# oled.net
KiCad netlist of a schematic drawn in Altium Designer
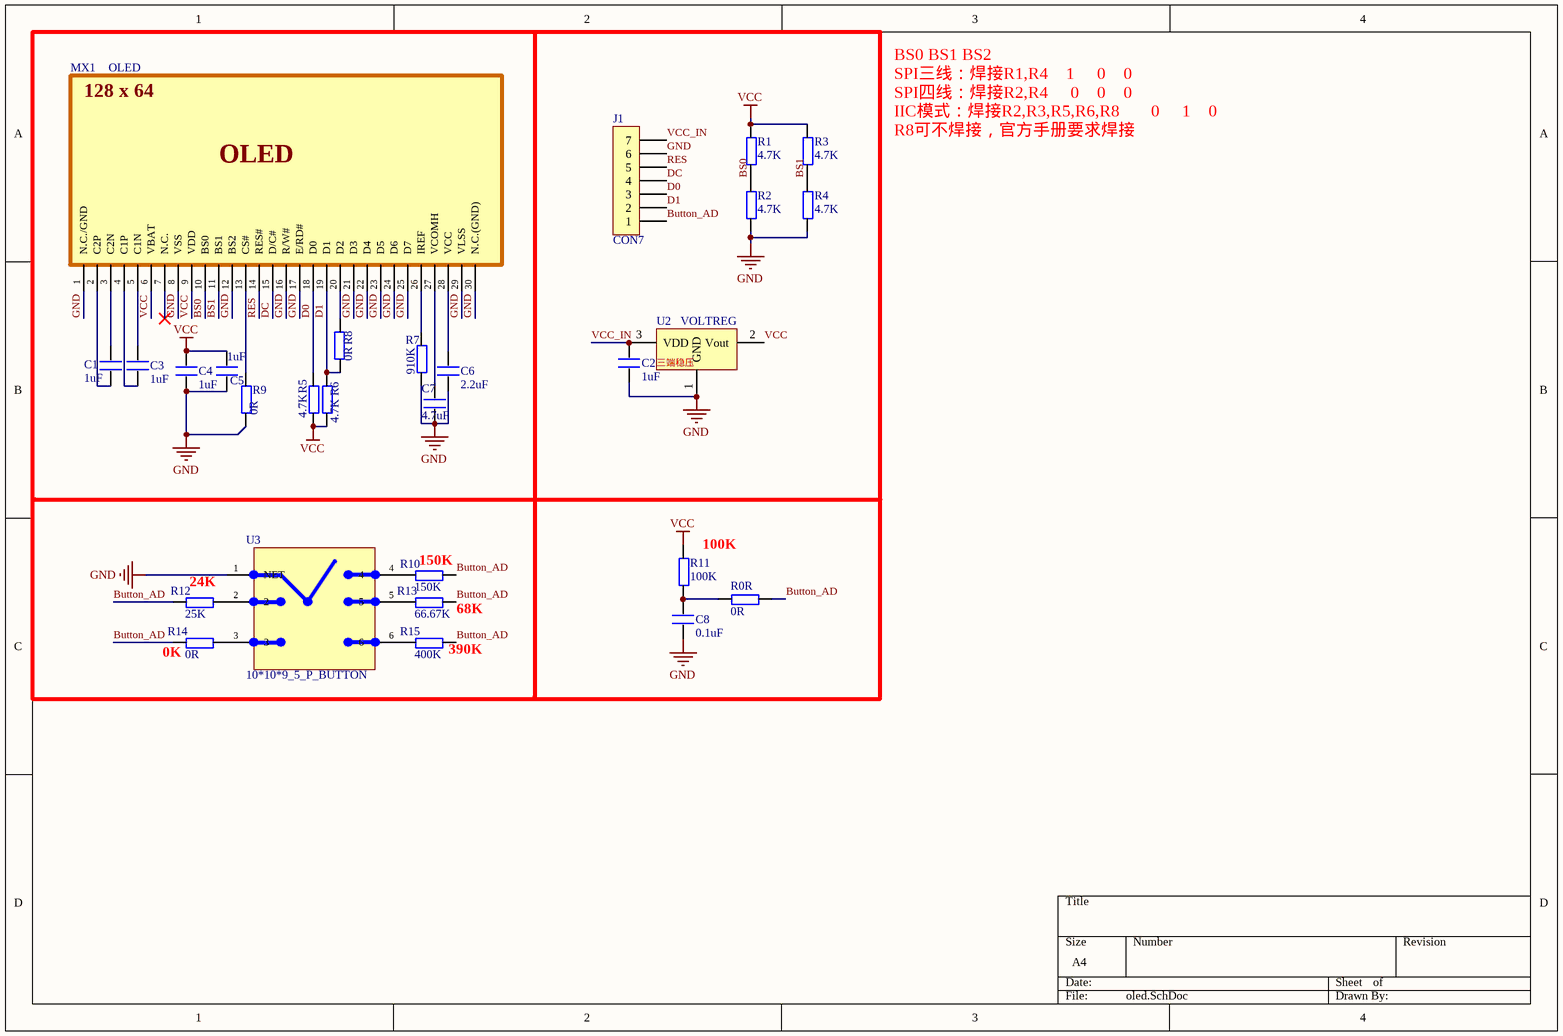
[diagram p0: oled.SchDoc]

(export (version "E")
  (design (tool "Eeschema 10.0.6"))
  (components
    (comp (ref "C1") (value "1uF") (footprint "0603P") (libsource (lib "0.96OLED") (part "C")))
    (comp (ref "C2") (value "1uF") (footprint "0603P") (libsource (lib "0.96OLED") (part "C")))
    (comp (ref "C3") (value "1uF") (footprint "0603P") (libsource (lib "0.96OLED") (part "C")))
    (comp (ref "C4") (value "1uF") (footprint "0603P") (libsource (lib "0.96OLED") (part "C")))
    (comp (ref "C5") (value "1uF") (footprint "0603P") (libsource (lib "0.96OLED") (part "C")))
    (comp (ref "C6") (value "2.2uF") (footprint "0603P") (libsource (lib "0.96OLED") (part "C")))
    (comp (ref "C7") (value "4.7uF") (footprint "0603P") (libsource (lib "0.96OLED") (part "C")))
    (comp (ref "C8") (value "0.1uF") (footprint "0603P") (libsource (lib "0.96OLED") (part "C")))
    (comp (ref "J1")
      (value "CON7")
      (footprint "Commonly:GH1.25-卧贴-7-Pin")
      (description "连接器")
      (libsource (lib "Connector") (part "CON7"))
    )
    (comp (ref "MX1") (value "OLED") (footprint "OLED") (libsource (lib "Chip") (part "OLED")))
    (comp (ref "R0R") (value "0R") (footprint "0603P") (libsource (lib "0.96OLED") (part "R")))
    (comp (ref "R1") (value "4.7K") (footprint "0603P") (libsource (lib "0.96OLED") (part "R")))
    (comp (ref "R2") (value "4.7K") (footprint "0603P") (libsource (lib "0.96OLED") (part "R")))
    (comp (ref "R3") (value "4.7K") (footprint "0603P") (libsource (lib "0.96OLED") (part "R")))
    (comp (ref "R4") (value "4.7K") (footprint "0603P") (libsource (lib "0.96OLED") (part "R")))
    (comp (ref "R5") (value "4.7K") (footprint "0603P") (libsource (lib "0.96OLED") (part "R")))
    (comp (ref "R6") (value "4.7K") (footprint "0603P") (libsource (lib "0.96OLED") (part "R")))
    (comp (ref "R7") (value "910K") (footprint "0603P") (libsource (lib "0.96OLED") (part "R")))
    (comp (ref "R8") (value "0R") (footprint "0603P") (libsource (lib "0.96OLED") (part "R")))
    (comp (ref "R9") (value "0R") (footprint "0603P") (libsource (lib "0.96OLED") (part "R")))
    (comp (ref "R10") (value "150K") (footprint "0603P") (libsource (lib "0.96OLED") (part "R")))
    (comp (ref "R11") (value "100K") (footprint "0603P") (libsource (lib "0.96OLED") (part "R")))
    (comp (ref "R12") (value "25K") (footprint "0603P") (libsource (lib "0.96OLED") (part "R")))
    (comp (ref "R13") (value "66.67K") (footprint "0603P") (libsource (lib "0.96OLED") (part "R")))
    (comp (ref "R14") (value "0R") (footprint "0603P") (libsource (lib "0.96OLED") (part "R")))
    (comp (ref "R15") (value "400K") (footprint "0603P") (libsource (lib "0.96OLED") (part "R")))
    (comp (ref "U2")
      (value "VOLTREG")
      (footprint "Chip:SOT-23-3")
      (description "三端稳压")
      (libsource (lib "Chip") (part "VOLTREG"))
    )
    (comp (ref "U3")
      (value "10*10*9_5_P_BUTTON")
      (footprint "10*10*9_5_P_BUTTON")
      (libsource (lib "Chip") (part "10*10*9_5_P_BUTTON"))
    )
  )
  (nets
    (net (code "1") (name "/BS0") (class "Default")
      (node (ref "MX1") (pin "10") (pinfunction "BS0_10") (pintype "passive"))
      (node (ref "R1") (pin "1") (pintype "passive"))
      (node (ref "R2") (pin "2") (pintype "passive"))
    )
    (net (code "2") (name "/BS1") (class "Default")
      (node (ref "MX1") (pin "11") (pinfunction "BS1_11") (pintype "passive"))
      (node (ref "R3") (pin "1") (pintype "passive"))
      (node (ref "R4") (pin "2") (pintype "passive"))
    )
    (net (code "3") (name "/Button_AD") (class "Default")
      (node (ref "J1") (pin "1") (pinfunction "1_1") (pintype "passive"))
      (node (ref "R0R") (pin "2") (pintype "passive"))
      (node (ref "R10") (pin "2") (pintype "passive"))
      (node (ref "R12") (pin "1") (pintype "passive"))
      (node (ref "R13") (pin "2") (pintype "passive"))
      (node (ref "R14") (pin "1") (pintype "passive"))
      (node (ref "R15") (pin "2") (pintype "passive"))
    )
    (net (code "4") (name "/D0") (class "Default")
      (node (ref "J1") (pin "3") (pinfunction "3_3") (pintype "passive"))
      (node (ref "MX1") (pin "18") (pinfunction "D0_18") (pintype "passive"))
      (node (ref "R5") (pin "2") (pintype "passive"))
    )
    (net (code "5") (name "/D1") (class "Default")
      (node (ref "J1") (pin "2") (pinfunction "2_2") (pintype "passive"))
      (node (ref "MX1") (pin "19") (pinfunction "D1_19") (pintype "passive"))
      (node (ref "R6") (pin "2") (pintype "passive"))
      (node (ref "R8") (pin "2") (pintype "passive"))
    )
    (net (code "6") (name "/DC") (class "Default")
      (node (ref "J1") (pin "4") (pinfunction "4_4") (pintype "passive"))
      (node (ref "MX1") (pin "15") (pinfunction "D/C#_15") (pintype "passive"))
    )
    (net (code "7") (name "/RES") (class "Default")
      (node (ref "J1") (pin "5") (pinfunction "5_5") (pintype "passive"))
      (node (ref "MX1") (pin "14") (pinfunction "RES#_14") (pintype "passive"))
    )
    (net (code "8") (name "/VCC_IN") (class "Default")
      (node (ref "C2") (pin "2") (pintype "passive"))
      (node (ref "J1") (pin "7") (pinfunction "7_7") (pintype "passive"))
      (node (ref "U2") (pin "3") (pinfunction "VDD_3") (pintype "passive"))
    )
    (net (code "9") (name "GND") (class "Default")
      (node (ref "C2") (pin "1") (pintype "passive"))
      (node (ref "C4") (pin "1") (pintype "passive"))
      (node (ref "C5") (pin "1") (pintype "passive"))
      (node (ref "C6") (pin "1") (pintype "passive"))
      (node (ref "C7") (pin "1") (pintype "passive"))
      (node (ref "C8") (pin "1") (pintype "passive"))
      (node (ref "J1") (pin "6") (pinfunction "6_6") (pintype "passive"))
      (node (ref "MX1") (pin "1") (pinfunction "N.C./GND_1") (pintype "passive"))
      (node (ref "MX1") (pin "12") (pinfunction "BS2_12") (pintype "passive"))
      (node (ref "MX1") (pin "16") (pinfunction "R/W#_16") (pintype "passive"))
      (node (ref "MX1") (pin "17") (pinfunction "E/RD#_17") (pintype "passive"))
      (node (ref "MX1") (pin "21") (pinfunction "D3_21") (pintype "passive"))
      (node (ref "MX1") (pin "22") (pinfunction "D4_22") (pintype "passive"))
      (node (ref "MX1") (pin "23") (pinfunction "D5_23") (pintype "passive"))
      (node (ref "MX1") (pin "24") (pinfunction "D6_24") (pintype "passive"))
      (node (ref "MX1") (pin "25") (pinfunction "D7_25") (pintype "passive"))
      (node (ref "MX1") (pin "29") (pinfunction "VLSS_29") (pintype "passive"))
      (node (ref "MX1") (pin "30") (pinfunction "N.C.(GND)_30") (pintype "passive"))
      (node (ref "MX1") (pin "8") (pinfunction "VSS_8") (pintype "passive"))
      (node (ref "R2") (pin "1") (pintype "passive"))
      (node (ref "R4") (pin "1") (pintype "passive"))
      (node (ref "R7") (pin "1") (pintype "passive"))
      (node (ref "R9") (pin "1") (pintype "passive"))
      (node (ref "U2") (pin "1") (pinfunction "GND_1") (pintype "passive"))
      (node (ref "U3") (pin "1") (pinfunction "NET_1") (pintype "passive"))
    )
    (net (code "10") (name "Net-(C8-Pad2)") (class "Default")
      (node (ref "C8") (pin "2") (pintype "passive"))
      (node (ref "R0R") (pin "1") (pintype "passive"))
      (node (ref "R11") (pin "1") (pintype "passive"))
    )
    (net (code "11") (name "Net-(MX1-C1N)") (class "Default")
      (node (ref "C3") (pin "2") (pintype "passive"))
      (node (ref "MX1") (pin "5") (pinfunction "C1N_5") (pintype "passive"))
    )
    (net (code "12") (name "Net-(MX1-C1P)") (class "Default")
      (node (ref "C3") (pin "1") (pintype "passive"))
      (node (ref "MX1") (pin "4") (pinfunction "C1P_4") (pintype "passive"))
    )
    (net (code "13") (name "Net-(MX1-C2N)") (class "Default")
      (node (ref "C1") (pin "2") (pintype "passive"))
      (node (ref "MX1") (pin "3") (pinfunction "C2N_3") (pintype "passive"))
    )
    (net (code "14") (name "Net-(MX1-C2P)") (class "Default")
      (node (ref "C1") (pin "1") (pintype "passive"))
      (node (ref "MX1") (pin "2") (pinfunction "C2P_2") (pintype "passive"))
    )
    (net (code "15") (name "Net-(MX1-CS#)") (class "Default")
      (node (ref "MX1") (pin "13") (pinfunction "CS#_13") (pintype "passive"))
      (node (ref "R9") (pin "2") (pintype "passive"))
    )
    (net (code "16") (name "Net-(MX1-D2)") (class "Default")
      (node (ref "MX1") (pin "20") (pinfunction "D2_20") (pintype "passive"))
      (node (ref "R8") (pin "1") (pintype "passive"))
    )
    (net (code "17") (name "Net-(MX1-IREF)") (class "Default")
      (node (ref "MX1") (pin "26") (pinfunction "IREF_26") (pintype "passive"))
      (node (ref "R7") (pin "2") (pintype "passive"))
    )
    (net (code "18") (name "Net-(MX1-VCC)") (class "Default")
      (node (ref "C6") (pin "2") (pintype "passive"))
      (node (ref "MX1") (pin "28") (pinfunction "VCC_28") (pintype "passive"))
    )
    (net (code "19") (name "Net-(MX1-VCOMH)") (class "Default")
      (node (ref "C7") (pin "2") (pintype "passive"))
      (node (ref "MX1") (pin "27") (pinfunction "VCOMH_27") (pintype "passive"))
    )
    (net (code "20") (name "Net-(R10-Pad1)") (class "Default")
      (node (ref "R10") (pin "1") (pintype "passive"))
      (node (ref "U3") (pin "4") (pinfunction "4_4") (pintype "passive"))
    )
    (net (code "21") (name "Net-(R12-Pad2)") (class "Default")
      (node (ref "R12") (pin "2") (pintype "passive"))
      (node (ref "U3") (pin "2") (pinfunction "2_2") (pintype "passive"))
    )
    (net (code "22") (name "Net-(R13-Pad1)") (class "Default")
      (node (ref "R13") (pin "1") (pintype "passive"))
      (node (ref "U3") (pin "5") (pinfunction "5_5") (pintype "passive"))
    )
    (net (code "23") (name "Net-(R14-Pad2)") (class "Default")
      (node (ref "R14") (pin "2") (pintype "passive"))
      (node (ref "U3") (pin "3") (pinfunction "3_3") (pintype "passive"))
    )
    (net (code "24") (name "Net-(R15-Pad1)") (class "Default")
      (node (ref "R15") (pin "1") (pintype "passive"))
      (node (ref "U3") (pin "6") (pinfunction "6_6") (pintype "passive"))
    )
    (net (code "25") (name "VCC") (class "Default")
      (node (ref "C4") (pin "2") (pintype "passive"))
      (node (ref "C5") (pin "2") (pintype "passive"))
      (node (ref "MX1") (pin "6") (pinfunction "VBAT_6") (pintype "passive"))
      (node (ref "MX1") (pin "9") (pinfunction "VDD_9") (pintype "passive"))
      (node (ref "R1") (pin "2") (pintype "passive"))
      (node (ref "R11") (pin "2") (pintype "passive"))
      (node (ref "R3") (pin "2") (pintype "passive"))
      (node (ref "R5") (pin "1") (pintype "passive"))
      (node (ref "R6") (pin "1") (pintype "passive"))
      (node (ref "U2") (pin "2") (pinfunction "Vout_2") (pintype "passive"))
    )
    (net (code "26") (name "unconnected-(MX1-N.C.-Pad7)") (class "Default")
      (node (ref "MX1") (pin "7") (pinfunction "N.C._7") (pintype "passive+no_connect"))
    )
  )
)
